# PennyMan_Ard_R3_Shield_v9_5.net
KiCad netlist of a schematic drawn in EAGLE
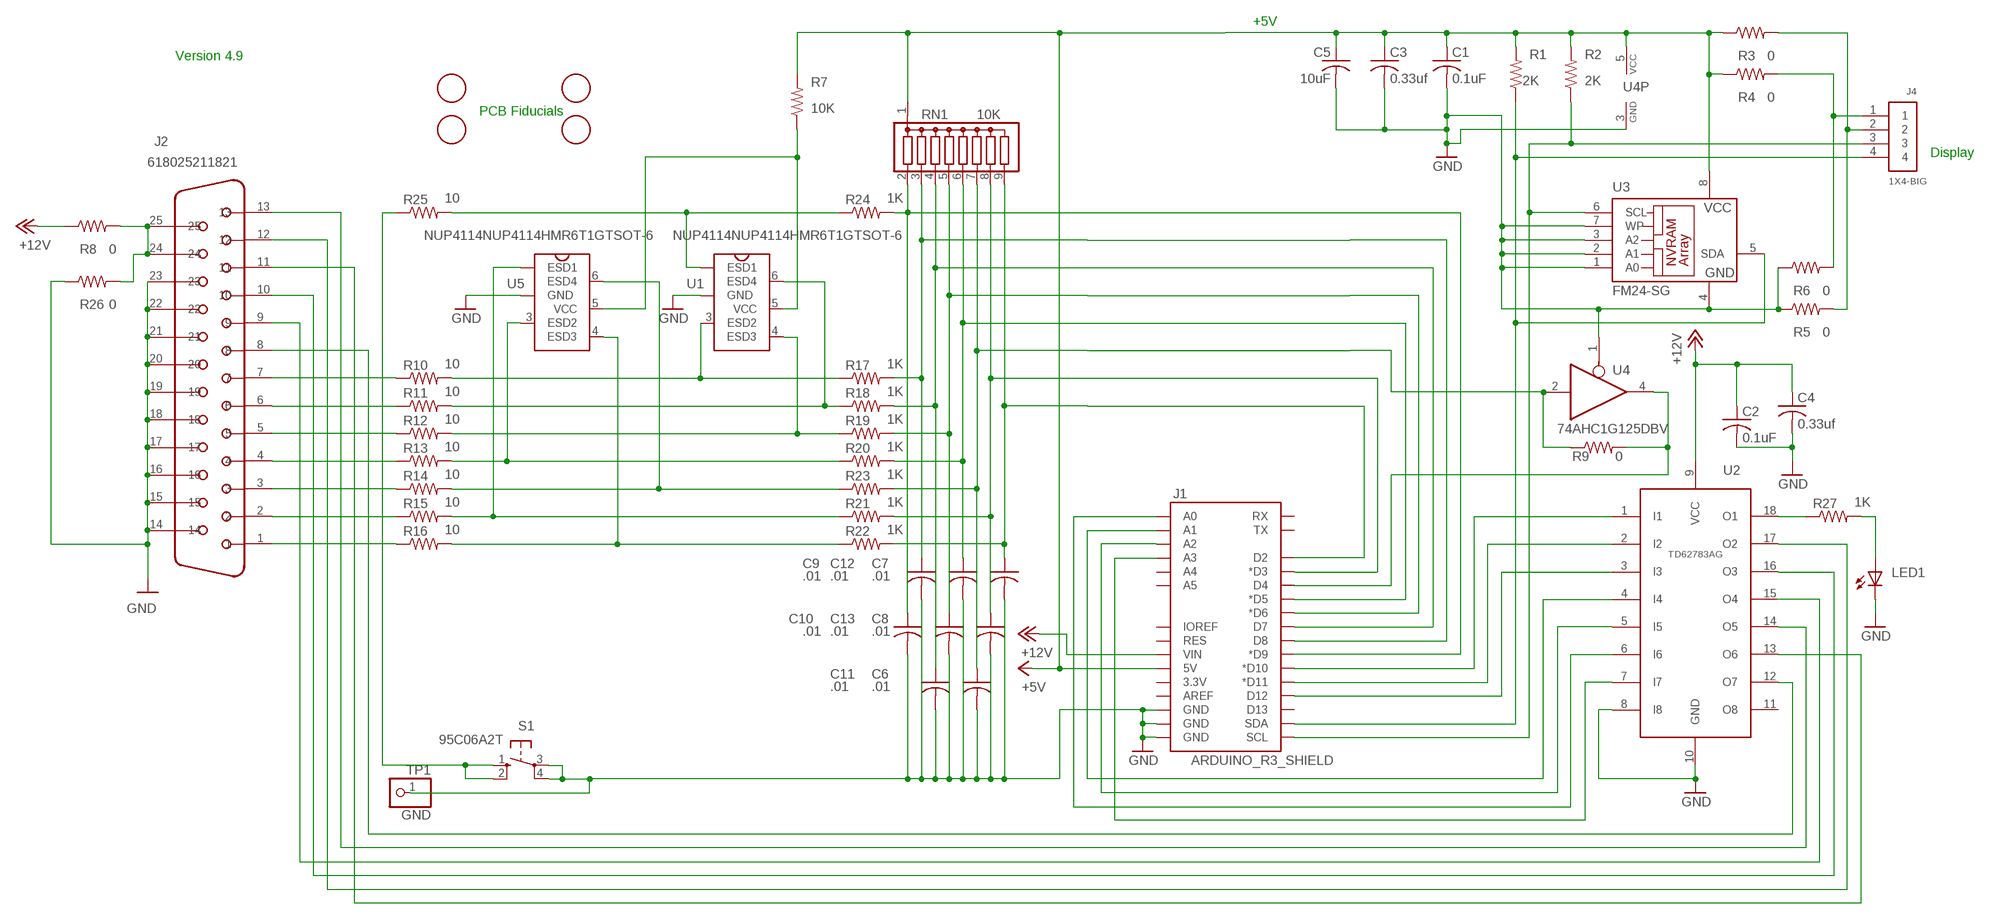
[diagram p0: schematic, sheet 1]

(export (version "E")
  (design (tool "Eeschema 10.0.6"))
  (components
    (comp (ref "C1")
      (value "0.1uF")
      (footprint "eagle-import:C0805")
      (libsource (lib "eagle-import") (part "resistor_C-USC0805"))
    )
    (comp (ref "C2")
      (value "0.1uF")
      (footprint "eagle-import:C0805")
      (libsource (lib "eagle-import") (part "resistor_C-USC0805"))
    )
    (comp (ref "C3")
      (value "0.33uf")
      (footprint "eagle-import:C1206")
      (libsource (lib "eagle-import") (part "resistor_C-USC1206"))
    )
    (comp (ref "C4")
      (value "0.33uf")
      (footprint "eagle-import:C1206")
      (libsource (lib "eagle-import") (part "resistor_C-USC1206"))
    )
    (comp (ref "C5")
      (value "10uF")
      (footprint "eagle-import:C1812")
      (libsource (lib "eagle-import") (part "resistor_C-USC1812"))
    )
    (comp (ref "C6")
      (value ".01")
      (footprint "eagle-import:C0805")
      (libsource (lib "eagle-import") (part "C-USC0805"))
    )
    (comp (ref "C7")
      (value ".01")
      (footprint "eagle-import:C0805")
      (libsource (lib "eagle-import") (part "C-USC0805"))
    )
    (comp (ref "C8")
      (value ".01")
      (footprint "eagle-import:C0805")
      (libsource (lib "eagle-import") (part "C-USC0805"))
    )
    (comp (ref "C9")
      (value ".01")
      (footprint "eagle-import:C0805")
      (libsource (lib "eagle-import") (part "C-USC0805"))
    )
    (comp (ref "C10")
      (value ".01")
      (footprint "eagle-import:C0805")
      (libsource (lib "eagle-import") (part "C-USC0805"))
    )
    (comp (ref "C11")
      (value ".01")
      (footprint "eagle-import:C0805")
      (libsource (lib "eagle-import") (part "C-USC0805"))
    )
    (comp (ref "C12")
      (value ".01")
      (footprint "eagle-import:C0805")
      (libsource (lib "eagle-import") (part "C-USC0805"))
    )
    (comp (ref "C13")
      (value ".01")
      (footprint "eagle-import:C0805")
      (libsource (lib "eagle-import") (part "C-USC0805"))
    )
    (comp (ref "GND")
      (value "TP1")
      (footprint "eagle-import:1X01")
      (libsource (lib "eagle-import") (part "PINHD-1X1"))
    )
    (comp (ref "J1")
      (value "ARDUINO_R3_SHIELD")
      (footprint "eagle-import:UNO_R3_SHIELD")
      (libsource (lib "eagle-import") (part "ARDUINO_R3_SHIELD"))
    )
    (comp (ref "J2")
      (value "618025211821")
      (footprint "eagle-import:618025211821")
      (libsource (lib "eagle-import") (part "618025211821"))
    )
    (comp (ref "J4")
      (value "1X4-BIG")
      (footprint "eagle-import:1X04-BIG")
      (libsource (lib "eagle-import") (part "1X4-BIG"))
    )
    (comp (ref "LED1")
      (value "LEDSMT1206")
      (footprint "eagle-import:1206")
      (libsource (lib "eagle-import") (part "LEDSMT1206"))
    )
    (comp (ref "R1")
      (value "2K")
      (footprint "eagle-import:R0805")
      (libsource (lib "eagle-import") (part "R-US_R0805"))
    )
    (comp (ref "R2")
      (value "2K")
      (footprint "eagle-import:R0805")
      (libsource (lib "eagle-import") (part "R-US_R0805"))
    )
    (comp (ref "R3")
      (value "0")
      (footprint "eagle-import:R0805")
      (libsource (lib "eagle-import") (part "R-US_R0805"))
    )
    (comp (ref "R4")
      (value "0")
      (footprint "eagle-import:R0805")
      (libsource (lib "eagle-import") (part "R-US_R0805"))
    )
    (comp (ref "R5")
      (value "0")
      (footprint "eagle-import:R0805")
      (libsource (lib "eagle-import") (part "R-US_R0805"))
    )
    (comp (ref "R6")
      (value "0")
      (footprint "eagle-import:R0805")
      (libsource (lib "eagle-import") (part "R-US_R0805"))
    )
    (comp (ref "R7")
      (value "10K")
      (footprint "eagle-import:R0805")
      (libsource (lib "eagle-import") (part "R-US_R0805"))
    )
    (comp (ref "R8")
      (value "0")
      (footprint "eagle-import:R0805")
      (libsource (lib "eagle-import") (part "R-US_R0805"))
    )
    (comp (ref "R9")
      (value "0")
      (footprint "eagle-import:R0805")
      (libsource (lib "eagle-import") (part "R-US_R0805"))
    )
    (comp (ref "R10")
      (value "10")
      (footprint "eagle-import:M0805")
      (libsource (lib "eagle-import") (part "resistor_348_R-US_M0805"))
    )
    (comp (ref "R11")
      (value "10")
      (footprint "eagle-import:M0805")
      (libsource (lib "eagle-import") (part "resistor_348_R-US_M0805"))
    )
    (comp (ref "R12")
      (value "10")
      (footprint "eagle-import:M0805")
      (libsource (lib "eagle-import") (part "resistor_348_R-US_M0805"))
    )
    (comp (ref "R13")
      (value "10")
      (footprint "eagle-import:M0805")
      (libsource (lib "eagle-import") (part "resistor_348_R-US_M0805"))
    )
    (comp (ref "R14")
      (value "10")
      (footprint "eagle-import:M0805")
      (libsource (lib "eagle-import") (part "resistor_348_R-US_M0805"))
    )
    (comp (ref "R15")
      (value "10")
      (footprint "eagle-import:M0805")
      (libsource (lib "eagle-import") (part "resistor_348_R-US_M0805"))
    )
    (comp (ref "R16")
      (value "10")
      (footprint "eagle-import:M0805")
      (libsource (lib "eagle-import") (part "resistor_348_R-US_M0805"))
    )
    (comp (ref "R17")
      (value "1K")
      (footprint "eagle-import:M0805")
      (libsource (lib "eagle-import") (part "resistor_348_R-US_M0805"))
    )
    (comp (ref "R18")
      (value "1K")
      (footprint "eagle-import:M0805")
      (libsource (lib "eagle-import") (part "resistor_348_R-US_M0805"))
    )
    (comp (ref "R19")
      (value "1K")
      (footprint "eagle-import:M0805")
      (libsource (lib "eagle-import") (part "resistor_348_R-US_M0805"))
    )
    (comp (ref "R20")
      (value "1K")
      (footprint "eagle-import:M0805")
      (libsource (lib "eagle-import") (part "resistor_348_R-US_M0805"))
    )
    (comp (ref "R21")
      (value "1K")
      (footprint "eagle-import:M0805")
      (libsource (lib "eagle-import") (part "resistor_348_R-US_M0805"))
    )
    (comp (ref "R22")
      (value "1K")
      (footprint "eagle-import:M0805")
      (libsource (lib "eagle-import") (part "resistor_348_R-US_M0805"))
    )
    (comp (ref "R23")
      (value "1K")
      (footprint "eagle-import:M0805")
      (libsource (lib "eagle-import") (part "resistor_348_R-US_M0805"))
    )
    (comp (ref "R24")
      (value "1K")
      (footprint "eagle-import:M0805")
      (libsource (lib "eagle-import") (part "resistor_348_R-US_M0805"))
    )
    (comp (ref "R25")
      (value "10")
      (footprint "eagle-import:M0805")
      (libsource (lib "eagle-import") (part "resistor_348_R-US_M0805"))
    )
    (comp (ref "R26")
      (value "0")
      (footprint "eagle-import:R0805")
      (libsource (lib "eagle-import") (part "R-US_R0805"))
    )
    (comp (ref "R27")
      (value "1K")
      (footprint "eagle-import:M0805")
      (libsource (lib "eagle-import") (part "resistor_348_R-US_M0805"))
    )
    (comp (ref "RN1")
      (value "10K")
      (footprint "eagle-import:SIL9")
      (libsource (lib "eagle-import") (part "G08R"))
    )
    (comp (ref "S1")
      (value "95C06A2T")
      (footprint "eagle-import:B3F-10XX")
      (libsource (lib "eagle-import") (part "10-XX"))
    )
    (comp (ref "U$1")
      (value "FIDUCIAL")
      (footprint "eagle-import:FIDUCIAL_1MM")
      (libsource (lib "eagle-import") (part "FIDUCIAL"))
    )
    (comp (ref "U$2")
      (value "FIDUCIAL")
      (footprint "eagle-import:FIDUCIAL_1MM")
      (libsource (lib "eagle-import") (part "FIDUCIAL"))
    )
    (comp (ref "U$3")
      (value "FIDUCIAL")
      (footprint "eagle-import:FIDUCIAL_1MM")
      (libsource (lib "eagle-import") (part "FIDUCIAL"))
    )
    (comp (ref "U$4")
      (value "FIDUCIAL")
      (footprint "eagle-import:FIDUCIAL_1MM")
      (libsource (lib "eagle-import") (part "FIDUCIAL"))
    )
    (comp (ref "U1")
      (value "NUP4114NUP4114HMR6T1GTSOT-6")
      (footprint "eagle-import:TSOT-23-6")
      (libsource (lib "eagle-import") (part "NUP4114TSOT-6NUP4114HMR6T1G"))
    )
    (comp (ref "U2")
      (value "TD62783AG")
      (footprint "eagle-import:SOP18")
      (libsource (lib "eagle-import") (part "TD62783AG"))
    )
    (comp (ref "U3")
      (value "FM24-SG")
      (footprint "eagle-import:SO8")
      (libsource (lib "eagle-import") (part "FM24-SG"))
    )
    (comp (ref "U4")
      (value "74AHC1G125DBV")
      (footprint "eagle-import:SOT23-5")
      (libsource (lib "eagle-import") (part "741G125DBVAHC"))
    )
    (comp (ref "U5")
      (value "NUP4114NUP4114HMR6T1GTSOT-6")
      (footprint "eagle-import:TSOT-23-6")
      (libsource (lib "eagle-import") (part "NUP4114TSOT-6NUP4114HMR6T1G"))
    )
  )
  (nets
    (net (code "1") (name "+5V") (class "Default")
      (node (ref "C1") (pin "1") (pinfunction "1_1") (pintype "passive"))
      (node (ref "C3") (pin "1") (pinfunction "1_1") (pintype "passive"))
      (node (ref "C5") (pin "1") (pinfunction "1_1") (pintype "passive"))
      (node (ref "J1") (pin "5V") (pinfunction "5V_5V") (pintype "bidirectional"))
      (node (ref "R1") (pin "2") (pinfunction "2_2") (pintype "passive"))
      (node (ref "R2") (pin "2") (pinfunction "2_2") (pintype "passive"))
      (node (ref "R3") (pin "1") (pinfunction "1_1") (pintype "passive"))
      (node (ref "R4") (pin "1") (pinfunction "1_1") (pintype "passive"))
      (node (ref "R7") (pin "2") (pinfunction "2_2") (pintype "passive"))
      (node (ref "RN1") (pin "1") (pinfunction "1_1") (pintype "passive"))
      (node (ref "U3") (pin "8") (pinfunction "VCC_8") (pintype "power_in"))
      (node (ref "U4") (pin "5") (pinfunction "VCC_5") (pintype "power_in"))
    )
    (net (code "2") (name "+12V") (class "Default")
      (node (ref "C2") (pin "1") (pinfunction "1_1") (pintype "passive"))
      (node (ref "C4") (pin "1") (pinfunction "1_1") (pintype "passive"))
      (node (ref "J1") (pin "VIN") (pinfunction "VIN_VIN") (pintype "bidirectional"))
      (node (ref "R8") (pin "1") (pinfunction "1_1") (pintype "passive"))
      (node (ref "U2") (pin "9") (pinfunction "VCC_9") (pintype "bidirectional"))
    )
    (net (code "3") (name "GND") (class "Default")
      (node (ref "C1") (pin "2") (pinfunction "2_2") (pintype "passive"))
      (node (ref "C10") (pin "2") (pinfunction "2_2") (pintype "passive"))
      (node (ref "C11") (pin "2") (pinfunction "2_2") (pintype "passive"))
      (node (ref "C12") (pin "2") (pinfunction "2_2") (pintype "passive"))
      (node (ref "C13") (pin "2") (pinfunction "2_2") (pintype "passive"))
      (node (ref "C2") (pin "2") (pinfunction "2_2") (pintype "passive"))
      (node (ref "C3") (pin "2") (pinfunction "2_2") (pintype "passive"))
      (node (ref "C4") (pin "2") (pinfunction "2_2") (pintype "passive"))
      (node (ref "C5") (pin "2") (pinfunction "2_2") (pintype "passive"))
      (node (ref "C6") (pin "2") (pinfunction "2_2") (pintype "passive"))
      (node (ref "C7") (pin "2") (pinfunction "2_2") (pintype "passive"))
      (node (ref "C8") (pin "2") (pinfunction "2_2") (pintype "passive"))
      (node (ref "C9") (pin "2") (pinfunction "2_2") (pintype "passive"))
      (node (ref "GND") (pin "1") (pinfunction "1_1") (pintype "passive"))
      (node (ref "J1") (pin "GND@0") (pinfunction "GND_GND@0") (pintype "bidirectional"))
      (node (ref "J1") (pin "GND@1") (pinfunction "GND_GND@1") (pintype "bidirectional"))
      (node (ref "J1") (pin "GND@2") (pinfunction "GND_GND@2") (pintype "bidirectional"))
      (node (ref "J2") (pin "14") (pinfunction "14_14") (pintype "bidirectional"))
      (node (ref "J2") (pin "15") (pinfunction "15_15") (pintype "bidirectional"))
      (node (ref "J2") (pin "16") (pinfunction "16_16") (pintype "bidirectional"))
      (node (ref "J2") (pin "17") (pinfunction "17_17") (pintype "bidirectional"))
      (node (ref "J2") (pin "18") (pinfunction "18_18") (pintype "bidirectional"))
      (node (ref "J2") (pin "19") (pinfunction "19_19") (pintype "bidirectional"))
      (node (ref "J2") (pin "20") (pinfunction "20_20") (pintype "bidirectional"))
      (node (ref "J2") (pin "21") (pinfunction "21_21") (pintype "bidirectional"))
      (node (ref "J2") (pin "22") (pinfunction "22_22") (pintype "bidirectional"))
      (node (ref "J2") (pin "23") (pinfunction "23_23") (pintype "bidirectional"))
      (node (ref "LED1") (pin "C") (pinfunction "C_C") (pintype "passive"))
      (node (ref "R26") (pin "1") (pinfunction "1_1") (pintype "passive"))
      (node (ref "R5") (pin "1") (pinfunction "1_1") (pintype "passive"))
      (node (ref "R6") (pin "1") (pinfunction "1_1") (pintype "passive"))
      (node (ref "S1") (pin "3") (pinfunction "P_3") (pintype "passive"))
      (node (ref "S1") (pin "4") (pinfunction "P1_4") (pintype "passive"))
      (node (ref "U1") (pin "2") (pinfunction "GND_2") (pintype "power_in"))
      (node (ref "U2") (pin "10") (pinfunction "GND_10") (pintype "bidirectional"))
      (node (ref "U2") (pin "8") (pinfunction "I8_8") (pintype "bidirectional"))
      (node (ref "U3") (pin "1") (pinfunction "A0_1") (pintype "passive"))
      (node (ref "U3") (pin "2") (pinfunction "A1_2") (pintype "passive"))
      (node (ref "U3") (pin "3") (pinfunction "A2_3") (pintype "passive"))
      (node (ref "U3") (pin "4") (pinfunction "GND_4") (pintype "power_in"))
      (node (ref "U3") (pin "7") (pinfunction "WP_7") (pintype "input"))
      (node (ref "U4") (pin "1") (pinfunction "OE_1") (pintype "input"))
      (node (ref "U4") (pin "3") (pinfunction "GND_3") (pintype "power_in"))
      (node (ref "U5") (pin "2") (pinfunction "GND_2") (pintype "power_in"))
    )
    (net (code "4") (name "Net-(C7-Pad1)") (class "Default")
      (node (ref "C7") (pin "1") (pinfunction "1_1") (pintype "passive"))
      (node (ref "J1") (pin "D2") (pinfunction "D2_D2") (pintype "bidirectional"))
      (node (ref "R22") (pin "2") (pinfunction "2_2") (pintype "passive"))
      (node (ref "RN1") (pin "9") (pinfunction "9_9") (pintype "passive"))
    )
    (net (code "5") (name "Net-(C11-Pad1)") (class "Default")
      (node (ref "C11") (pin "1") (pinfunction "1_1") (pintype "passive"))
      (node (ref "J1") (pin "D7") (pinfunction "D7_D7") (pintype "bidirectional"))
      (node (ref "R18") (pin "2") (pinfunction "2_2") (pintype "passive"))
      (node (ref "RN1") (pin "4") (pinfunction "4_4") (pintype "passive"))
    )
    (net (code "6") (name "Net-(C12-Pad1)") (class "Default")
      (node (ref "C12") (pin "1") (pinfunction "1_1") (pintype "passive"))
      (node (ref "J1") (pin "D8") (pinfunction "D8_D8") (pintype "bidirectional"))
      (node (ref "R17") (pin "2") (pinfunction "2_2") (pintype "passive"))
      (node (ref "RN1") (pin "3") (pinfunction "3_3") (pintype "passive"))
    )
    (net (code "7") (name "Net-(J1-*D3)") (class "Default")
      (node (ref "C8") (pin "1") (pinfunction "1_1") (pintype "passive"))
      (node (ref "J1") (pin "D3") (pinfunction "*D3_D3") (pintype "bidirectional"))
      (node (ref "R21") (pin "2") (pinfunction "2_2") (pintype "passive"))
      (node (ref "RN1") (pin "8") (pinfunction "8_8") (pintype "passive"))
    )
    (net (code "8") (name "Net-(J1-*D5)") (class "Default")
      (node (ref "C9") (pin "1") (pinfunction "1_1") (pintype "passive"))
      (node (ref "J1") (pin "D5") (pinfunction "*D5_D5") (pintype "bidirectional"))
      (node (ref "R20") (pin "2") (pinfunction "2_2") (pintype "passive"))
      (node (ref "RN1") (pin "6") (pinfunction "6_6") (pintype "passive"))
    )
    (net (code "9") (name "Net-(J1-*D6)") (class "Default")
      (node (ref "C10") (pin "1") (pinfunction "1_1") (pintype "passive"))
      (node (ref "J1") (pin "D6") (pinfunction "*D6_D6") (pintype "bidirectional"))
      (node (ref "R19") (pin "2") (pinfunction "2_2") (pintype "passive"))
      (node (ref "RN1") (pin "5") (pinfunction "5_5") (pintype "passive"))
    )
    (net (code "10") (name "Net-(J1-*D9)") (class "Default")
      (node (ref "C13") (pin "1") (pinfunction "1_1") (pintype "passive"))
      (node (ref "J1") (pin "D9") (pinfunction "*D9_D9") (pintype "bidirectional"))
      (node (ref "R24") (pin "2") (pinfunction "2_2") (pintype "passive"))
      (node (ref "RN1") (pin "2") (pinfunction "2_2") (pintype "passive"))
    )
    (net (code "11") (name "Net-(J1-*D10)") (class "Default")
      (node (ref "J1") (pin "D10") (pinfunction "*D10_D10") (pintype "bidirectional"))
      (node (ref "U2") (pin "1") (pinfunction "I1_1") (pintype "bidirectional"))
    )
    (net (code "12") (name "Net-(J1-*D11)") (class "Default")
      (node (ref "J1") (pin "D11") (pinfunction "*D11_D11") (pintype "bidirectional"))
      (node (ref "U2") (pin "2") (pinfunction "I2_2") (pintype "bidirectional"))
    )
    (net (code "13") (name "Net-(J2-Pad1)") (class "Default")
      (node (ref "J2") (pin "1") (pinfunction "1_1") (pintype "bidirectional"))
      (node (ref "R16") (pin "1") (pinfunction "1_1") (pintype "passive"))
    )
    (net (code "14") (name "Net-(J2-Pad2)") (class "Default")
      (node (ref "J2") (pin "2") (pinfunction "2_2") (pintype "bidirectional"))
      (node (ref "R15") (pin "1") (pinfunction "1_1") (pintype "passive"))
    )
    (net (code "15") (name "Net-(J2-Pad3)") (class "Default")
      (node (ref "J2") (pin "3") (pinfunction "3_3") (pintype "bidirectional"))
      (node (ref "R14") (pin "1") (pinfunction "1_1") (pintype "passive"))
    )
    (net (code "16") (name "Net-(J2-Pad4)") (class "Default")
      (node (ref "J2") (pin "4") (pinfunction "4_4") (pintype "bidirectional"))
      (node (ref "R13") (pin "1") (pinfunction "1_1") (pintype "passive"))
    )
    (net (code "17") (name "Net-(J2-Pad5)") (class "Default")
      (node (ref "J2") (pin "5") (pinfunction "5_5") (pintype "bidirectional"))
      (node (ref "R12") (pin "1") (pinfunction "1_1") (pintype "passive"))
    )
    (net (code "18") (name "Net-(J2-Pad6)") (class "Default")
      (node (ref "J2") (pin "6") (pinfunction "6_6") (pintype "bidirectional"))
      (node (ref "R11") (pin "1") (pinfunction "1_1") (pintype "passive"))
    )
    (net (code "19") (name "Net-(J2-Pad7)") (class "Default")
      (node (ref "J2") (pin "7") (pinfunction "7_7") (pintype "bidirectional"))
      (node (ref "R10") (pin "1") (pinfunction "1_1") (pintype "passive"))
    )
    (net (code "20") (name "Net-(J2-Pad24)") (class "Default")
      (node (ref "J2") (pin "24") (pinfunction "24_24") (pintype "bidirectional"))
      (node (ref "J2") (pin "25") (pinfunction "25_25") (pintype "bidirectional"))
      (node (ref "R26") (pin "2") (pinfunction "2_2") (pintype "passive"))
      (node (ref "R8") (pin "2") (pinfunction "2_2") (pintype "passive"))
    )
    (net (code "21") (name "Net-(J4-Pad1)") (class "Default")
      (node (ref "J4") (pin "1") (pinfunction "1_1") (pintype "bidirectional"))
      (node (ref "R4") (pin "2") (pinfunction "2_2") (pintype "passive"))
      (node (ref "R6") (pin "2") (pinfunction "2_2") (pintype "passive"))
    )
    (net (code "22") (name "Net-(J4-Pad2)") (class "Default")
      (node (ref "J4") (pin "2") (pinfunction "2_2") (pintype "bidirectional"))
      (node (ref "R3") (pin "2") (pinfunction "2_2") (pintype "passive"))
      (node (ref "R5") (pin "2") (pinfunction "2_2") (pintype "passive"))
    )
    (net (code "23") (name "Net-(LED1-PadA)") (class "Default")
      (node (ref "LED1") (pin "A") (pinfunction "A_A") (pintype "passive"))
      (node (ref "R27") (pin "2") (pinfunction "2_2") (pintype "passive"))
    )
    (net (code "24") (name "Net-(S1-S)") (class "Default")
      (node (ref "R25") (pin "1") (pinfunction "1_1") (pintype "passive"))
      (node (ref "S1") (pin "1") (pinfunction "S_1") (pintype "passive"))
      (node (ref "S1") (pin "2") (pinfunction "S1_2") (pintype "passive"))
    )
    (net (code "25") (name "Net-(U1-ESD1)") (class "Default")
      (node (ref "R24") (pin "1") (pinfunction "1_1") (pintype "passive"))
      (node (ref "R25") (pin "2") (pinfunction "2_2") (pintype "passive"))
      (node (ref "U1") (pin "1") (pinfunction "ESD1_1") (pintype "bidirectional"))
    )
    (net (code "26") (name "Net-(U1-ESD2)") (class "Default")
      (node (ref "R10") (pin "2") (pinfunction "2_2") (pintype "passive"))
      (node (ref "R17") (pin "1") (pinfunction "1_1") (pintype "passive"))
      (node (ref "U1") (pin "3") (pinfunction "ESD2_3") (pintype "bidirectional"))
    )
    (net (code "27") (name "Net-(U1-ESD3)") (class "Default")
      (node (ref "R12") (pin "2") (pinfunction "2_2") (pintype "passive"))
      (node (ref "R19") (pin "1") (pinfunction "1_1") (pintype "passive"))
      (node (ref "U1") (pin "4") (pinfunction "ESD3_4") (pintype "bidirectional"))
    )
    (net (code "28") (name "Net-(U1-ESD4)") (class "Default")
      (node (ref "R11") (pin "2") (pinfunction "2_2") (pintype "passive"))
      (node (ref "R18") (pin "1") (pinfunction "1_1") (pintype "passive"))
      (node (ref "U1") (pin "6") (pinfunction "ESD4_6") (pintype "bidirectional"))
    )
    (net (code "29") (name "Net-(U1-VCC)") (class "Default")
      (node (ref "R7") (pin "1") (pinfunction "1_1") (pintype "passive"))
      (node (ref "U1") (pin "5") (pinfunction "VCC_5") (pintype "power_in"))
      (node (ref "U5") (pin "5") (pinfunction "VCC_5") (pintype "power_in"))
    )
    (net (code "30") (name "Net-(U2-I3)") (class "Default")
      (node (ref "J1") (pin "D12") (pinfunction "D12_D12") (pintype "bidirectional"))
      (node (ref "U2") (pin "3") (pinfunction "I3_3") (pintype "bidirectional"))
    )
    (net (code "31") (name "Net-(U2-I4)") (class "Default")
      (node (ref "J1") (pin "A1") (pinfunction "A1_A1") (pintype "bidirectional"))
      (node (ref "U2") (pin "4") (pinfunction "I4_4") (pintype "bidirectional"))
    )
    (net (code "32") (name "Net-(U2-I5)") (class "Default")
      (node (ref "J1") (pin "A2") (pinfunction "A2_A2") (pintype "bidirectional"))
      (node (ref "U2") (pin "5") (pinfunction "I5_5") (pintype "bidirectional"))
    )
    (net (code "33") (name "Net-(U2-I6)") (class "Default")
      (node (ref "J1") (pin "A0") (pinfunction "A0_A0") (pintype "bidirectional"))
      (node (ref "U2") (pin "6") (pinfunction "I6_6") (pintype "bidirectional"))
    )
    (net (code "34") (name "Net-(U2-I7)") (class "Default")
      (node (ref "J1") (pin "A3") (pinfunction "A3_A3") (pintype "bidirectional"))
      (node (ref "U2") (pin "7") (pinfunction "I7_7") (pintype "bidirectional"))
    )
    (net (code "35") (name "Net-(U2-O1)") (class "Default")
      (node (ref "R27") (pin "1") (pinfunction "1_1") (pintype "passive"))
      (node (ref "U2") (pin "18") (pinfunction "O1_18") (pintype "bidirectional"))
    )
    (net (code "36") (name "Net-(U2-O2)") (class "Default")
      (node (ref "J2") (pin "12") (pinfunction "12_12") (pintype "bidirectional"))
      (node (ref "U2") (pin "17") (pinfunction "O2_17") (pintype "bidirectional"))
    )
    (net (code "37") (name "Net-(U2-O3)") (class "Default")
      (node (ref "J2") (pin "10") (pinfunction "10_10") (pintype "bidirectional"))
      (node (ref "U2") (pin "16") (pinfunction "O3_16") (pintype "bidirectional"))
    )
    (net (code "38") (name "Net-(U2-O4)") (class "Default")
      (node (ref "J2") (pin "9") (pinfunction "9_9") (pintype "bidirectional"))
      (node (ref "U2") (pin "15") (pinfunction "O4_15") (pintype "bidirectional"))
    )
    (net (code "39") (name "Net-(U2-O5)") (class "Default")
      (node (ref "J2") (pin "13") (pinfunction "13_13") (pintype "bidirectional"))
      (node (ref "U2") (pin "14") (pinfunction "O5_14") (pintype "bidirectional"))
    )
    (net (code "40") (name "Net-(U2-O6)") (class "Default")
      (node (ref "J2") (pin "11") (pinfunction "11_11") (pintype "bidirectional"))
      (node (ref "U2") (pin "13") (pinfunction "O6_13") (pintype "bidirectional"))
    )
    (net (code "41") (name "Net-(U2-O7)") (class "Default")
      (node (ref "J2") (pin "8") (pinfunction "8_8") (pintype "bidirectional"))
      (node (ref "U2") (pin "12") (pinfunction "O7_12") (pintype "bidirectional"))
    )
    (net (code "42") (name "Net-(U3-SCL)") (class "Default")
      (node (ref "J1") (pin "SCL") (pinfunction "SCL_SCL") (pintype "bidirectional"))
      (node (ref "J4") (pin "3") (pinfunction "3_3") (pintype "bidirectional"))
      (node (ref "R2") (pin "1") (pinfunction "1_1") (pintype "passive"))
      (node (ref "U3") (pin "6") (pinfunction "SCL_6") (pintype "input"))
    )
    (net (code "43") (name "Net-(U3-SDA)") (class "Default")
      (node (ref "J1") (pin "SDA") (pinfunction "SDA_SDA") (pintype "bidirectional"))
      (node (ref "J4") (pin "4") (pinfunction "4_4") (pintype "bidirectional"))
      (node (ref "R1") (pin "1") (pinfunction "1_1") (pintype "passive"))
      (node (ref "U3") (pin "5") (pinfunction "SDA_5") (pintype "bidirectional"))
    )
    (net (code "44") (name "Net-(U4A-I)") (class "Default")
      (node (ref "C6") (pin "1") (pinfunction "1_1") (pintype "passive"))
      (node (ref "R23") (pin "2") (pinfunction "2_2") (pintype "passive"))
      (node (ref "R9") (pin "1") (pinfunction "1_1") (pintype "passive"))
      (node (ref "RN1") (pin "7") (pinfunction "7_7") (pintype "passive"))
      (node (ref "U4") (pin "2") (pinfunction "I_2") (pintype "input"))
    )
    (net (code "45") (name "Net-(U4A-O)") (class "Default")
      (node (ref "J1") (pin "D4") (pinfunction "D4_D4") (pintype "bidirectional"))
      (node (ref "R9") (pin "2") (pinfunction "2_2") (pintype "passive"))
      (node (ref "U4") (pin "4") (pinfunction "O_4") (pintype "tri_state"))
    )
    (net (code "46") (name "Net-(U5-ESD1)") (class "Default")
      (node (ref "R15") (pin "2") (pinfunction "2_2") (pintype "passive"))
      (node (ref "R21") (pin "1") (pinfunction "1_1") (pintype "passive"))
      (node (ref "U5") (pin "1") (pinfunction "ESD1_1") (pintype "bidirectional"))
    )
    (net (code "47") (name "Net-(U5-ESD2)") (class "Default")
      (node (ref "R13") (pin "2") (pinfunction "2_2") (pintype "passive"))
      (node (ref "R20") (pin "1") (pinfunction "1_1") (pintype "passive"))
      (node (ref "U5") (pin "3") (pinfunction "ESD2_3") (pintype "bidirectional"))
    )
    (net (code "48") (name "Net-(U5-ESD3)") (class "Default")
      (node (ref "R16") (pin "2") (pinfunction "2_2") (pintype "passive"))
      (node (ref "R22") (pin "1") (pinfunction "1_1") (pintype "passive"))
      (node (ref "U5") (pin "4") (pinfunction "ESD3_4") (pintype "bidirectional"))
    )
    (net (code "49") (name "Net-(U5-ESD4)") (class "Default")
      (node (ref "R14") (pin "2") (pinfunction "2_2") (pintype "passive"))
      (node (ref "R23") (pin "1") (pinfunction "1_1") (pintype "passive"))
      (node (ref "U5") (pin "6") (pinfunction "ESD4_6") (pintype "bidirectional"))
    )
    (net (code "50") (name "unconnected-(J1-Pad3.3V)") (class "Default")
      (node (ref "J1") (pin "3.3V") (pinfunction "3.3V_3.3V") (pintype "bidirectional"))
    )
    (net (code "51") (name "unconnected-(J1-PadA4)") (class "Default")
      (node (ref "J1") (pin "A4") (pinfunction "A4_A4") (pintype "bidirectional"))
    )
    (net (code "52") (name "unconnected-(J1-PadA5)") (class "Default")
      (node (ref "J1") (pin "A5") (pinfunction "A5_A5") (pintype "bidirectional"))
    )
    (net (code "53") (name "unconnected-(J1-PadAREF)") (class "Default")
      (node (ref "J1") (pin "AREF") (pinfunction "AREF_AREF") (pintype "bidirectional"))
    )
    (net (code "54") (name "unconnected-(J1-PadD13)") (class "Default")
      (node (ref "J1") (pin "D13") (pinfunction "D13_D13") (pintype "bidirectional"))
    )
    (net (code "55") (name "unconnected-(J1-PadIOREF)") (class "Default")
      (node (ref "J1") (pin "IOREF") (pinfunction "IOREF_IOREF") (pintype "bidirectional"))
    )
    (net (code "56") (name "unconnected-(J1-PadRES)") (class "Default")
      (node (ref "J1") (pin "RES") (pinfunction "RES_RES") (pintype "bidirectional"))
    )
    (net (code "57") (name "unconnected-(J1-PadRX)") (class "Default")
      (node (ref "J1") (pin "RX") (pinfunction "RX_RX") (pintype "bidirectional"))
    )
    (net (code "58") (name "unconnected-(J1-PadTX)") (class "Default")
      (node (ref "J1") (pin "TX") (pinfunction "TX_TX") (pintype "bidirectional"))
    )
    (net (code "59") (name "unconnected-(U2-O8-Pad11)") (class "Default")
      (node (ref "U2") (pin "11") (pinfunction "O8_11") (pintype "bidirectional"))
    )
  )
)
